# EP4CE6E22C8.net
KiCad netlist of a schematic drawn in Altium Designer
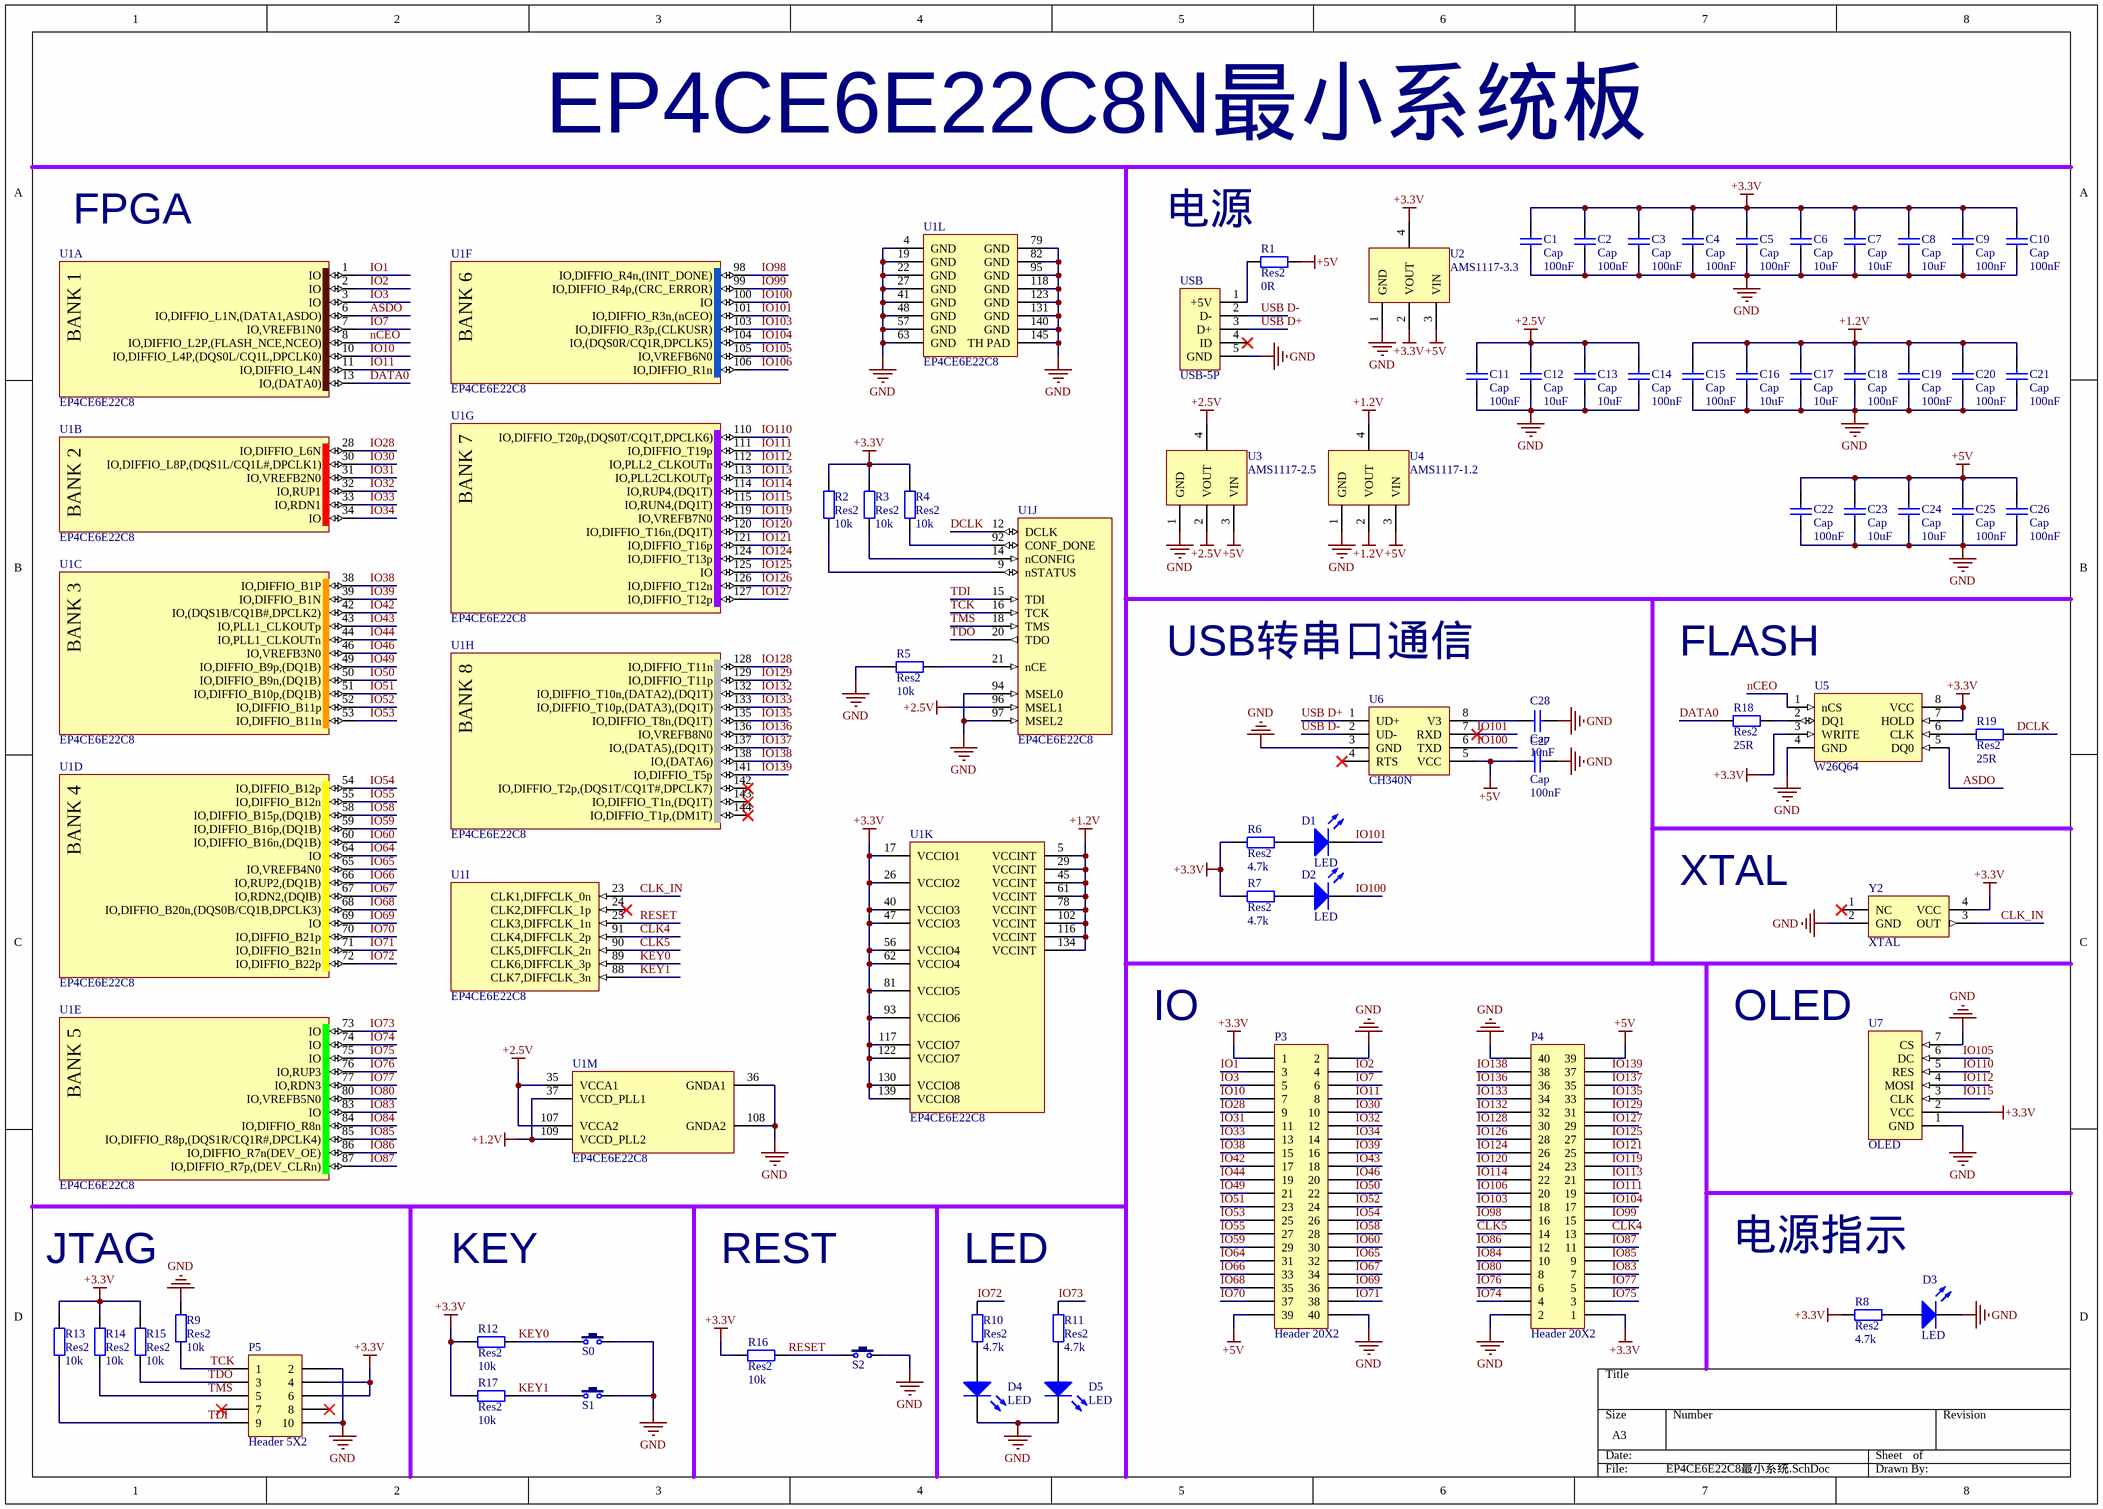
[diagram p0: EP4CE6E22C8最小系统.SchDoc]

(export (version "E")
  (design (tool "Eeschema 10.0.6"))
  (components
    (comp (ref "C1")
      (value "Cap")
      (footprint "C 0603")
      (description "Capacitor")
      (fields (field (name "ALTIUM_VALUE") "100nF") (field (name "PUBLISHER") "Altium Limited"))
      (libsource (lib "Miscellaneous Devices") (part "Cap"))
    )
    (comp (ref "C2")
      (value "Cap")
      (footprint "C 0603")
      (description "Capacitor")
      (fields (field (name "ALTIUM_VALUE") "100nF") (field (name "PUBLISHER") "Altium Limited"))
      (libsource (lib "Miscellaneous Devices") (part "Cap"))
    )
    (comp (ref "C3")
      (value "Cap")
      (footprint "C 0603")
      (description "Capacitor")
      (fields (field (name "ALTIUM_VALUE") "100nF") (field (name "PUBLISHER") "Altium Limited"))
      (libsource (lib "Miscellaneous Devices") (part "Cap"))
    )
    (comp (ref "C4")
      (value "Cap")
      (footprint "C 0603")
      (description "Capacitor")
      (fields (field (name "ALTIUM_VALUE") "100nF") (field (name "PUBLISHER") "Altium Limited"))
      (libsource (lib "Miscellaneous Devices") (part "Cap"))
    )
    (comp (ref "C5")
      (value "Cap")
      (footprint "C 0603")
      (description "Capacitor")
      (fields (field (name "ALTIUM_VALUE") "100nF") (field (name "PUBLISHER") "Altium Limited"))
      (libsource (lib "Miscellaneous Devices") (part "Cap"))
    )
    (comp (ref "C6")
      (value "Cap")
      (footprint "C 0603")
      (description "Capacitor")
      (fields (field (name "ALTIUM_VALUE") "10uF") (field (name "PUBLISHER") "Altium Limited"))
      (libsource (lib "Miscellaneous Devices") (part "Cap"))
    )
    (comp (ref "C7")
      (value "Cap")
      (footprint "C 0603")
      (description "Capacitor")
      (fields (field (name "ALTIUM_VALUE") "10uF") (field (name "PUBLISHER") "Altium Limited"))
      (libsource (lib "Miscellaneous Devices") (part "Cap"))
    )
    (comp (ref "C8")
      (value "Cap")
      (footprint "C 0603")
      (description "Capacitor")
      (fields (field (name "ALTIUM_VALUE") "10uF") (field (name "PUBLISHER") "Altium Limited"))
      (libsource (lib "Miscellaneous Devices") (part "Cap"))
    )
    (comp (ref "C9")
      (value "Cap")
      (footprint "C 0603")
      (description "Capacitor")
      (fields (field (name "ALTIUM_VALUE") "100nF") (field (name "PUBLISHER") "Altium Limited"))
      (libsource (lib "Miscellaneous Devices") (part "Cap"))
    )
    (comp (ref "C10")
      (value "Cap")
      (footprint "C 0603")
      (description "Capacitor")
      (fields (field (name "ALTIUM_VALUE") "100nF") (field (name "PUBLISHER") "Altium Limited"))
      (libsource (lib "Miscellaneous Devices") (part "Cap"))
    )
    (comp (ref "C11")
      (value "Cap")
      (footprint "C 0603")
      (description "Capacitor")
      (fields (field (name "ALTIUM_VALUE") "100nF") (field (name "PUBLISHER") "Altium Limited"))
      (libsource (lib "Miscellaneous Devices") (part "Cap"))
    )
    (comp (ref "C12")
      (value "Cap")
      (footprint "C 0603")
      (description "Capacitor")
      (fields (field (name "ALTIUM_VALUE") "10uF") (field (name "PUBLISHER") "Altium Limited"))
      (libsource (lib "Miscellaneous Devices") (part "Cap"))
    )
    (comp (ref "C13")
      (value "Cap")
      (footprint "C 0603")
      (description "Capacitor")
      (fields (field (name "ALTIUM_VALUE") "10uF") (field (name "PUBLISHER") "Altium Limited"))
      (libsource (lib "Miscellaneous Devices") (part "Cap"))
    )
    (comp (ref "C14")
      (value "Cap")
      (footprint "C 0603")
      (description "Capacitor")
      (fields (field (name "ALTIUM_VALUE") "100nF") (field (name "PUBLISHER") "Altium Limited"))
      (libsource (lib "Miscellaneous Devices") (part "Cap"))
    )
    (comp (ref "C15")
      (value "Cap")
      (footprint "C 0603")
      (description "Capacitor")
      (fields (field (name "ALTIUM_VALUE") "100nF") (field (name "PUBLISHER") "Altium Limited"))
      (libsource (lib "Miscellaneous Devices") (part "Cap"))
    )
    (comp (ref "C16")
      (value "Cap")
      (footprint "C 0603")
      (description "Capacitor")
      (fields (field (name "ALTIUM_VALUE") "10uF") (field (name "PUBLISHER") "Altium Limited"))
      (libsource (lib "Miscellaneous Devices") (part "Cap"))
    )
    (comp (ref "C17")
      (value "Cap")
      (footprint "C 0603")
      (description "Capacitor")
      (fields (field (name "ALTIUM_VALUE") "10uF") (field (name "PUBLISHER") "Altium Limited"))
      (libsource (lib "Miscellaneous Devices") (part "Cap"))
    )
    (comp (ref "C18")
      (value "Cap")
      (footprint "C 0603")
      (description "Capacitor")
      (fields (field (name "ALTIUM_VALUE") "100nF") (field (name "PUBLISHER") "Altium Limited"))
      (libsource (lib "Miscellaneous Devices") (part "Cap"))
    )
    (comp (ref "C19")
      (value "Cap")
      (footprint "C 0603")
      (description "Capacitor")
      (fields (field (name "ALTIUM_VALUE") "100nF") (field (name "PUBLISHER") "Altium Limited"))
      (libsource (lib "Miscellaneous Devices") (part "Cap"))
    )
    (comp (ref "C20")
      (value "Cap")
      (footprint "C 0603")
      (description "Capacitor")
      (fields (field (name "ALTIUM_VALUE") "100nF") (field (name "PUBLISHER") "Altium Limited"))
      (libsource (lib "Miscellaneous Devices") (part "Cap"))
    )
    (comp (ref "C21")
      (value "Cap")
      (footprint "C 0603")
      (description "Capacitor")
      (fields (field (name "ALTIUM_VALUE") "100nF") (field (name "PUBLISHER") "Altium Limited"))
      (libsource (lib "Miscellaneous Devices") (part "Cap"))
    )
    (comp (ref "C22")
      (value "Cap")
      (footprint "C 0603")
      (description "Capacitor")
      (fields (field (name "ALTIUM_VALUE") "100nF") (field (name "PUBLISHER") "Altium Limited"))
      (libsource (lib "Miscellaneous Devices") (part "Cap"))
    )
    (comp (ref "C23")
      (value "Cap")
      (footprint "C 0603")
      (description "Capacitor")
      (fields (field (name "ALTIUM_VALUE") "10uF") (field (name "PUBLISHER") "Altium Limited"))
      (libsource (lib "Miscellaneous Devices") (part "Cap"))
    )
    (comp (ref "C24")
      (value "Cap")
      (footprint "C 0603")
      (description "Capacitor")
      (fields (field (name "ALTIUM_VALUE") "10uF") (field (name "PUBLISHER") "Altium Limited"))
      (libsource (lib "Miscellaneous Devices") (part "Cap"))
    )
    (comp (ref "C25")
      (value "Cap")
      (footprint "C 0603")
      (description "Capacitor")
      (fields (field (name "ALTIUM_VALUE") "100nF") (field (name "PUBLISHER") "Altium Limited"))
      (libsource (lib "Miscellaneous Devices") (part "Cap"))
    )
    (comp (ref "C26")
      (value "Cap")
      (footprint "C 0603")
      (description "Capacitor")
      (fields (field (name "ALTIUM_VALUE") "100nF") (field (name "PUBLISHER") "Altium Limited"))
      (libsource (lib "Miscellaneous Devices") (part "Cap"))
    )
    (comp (ref "C27")
      (value "Cap")
      (footprint "C 0603")
      (description "Capacitor (Semiconductor SIM Model)")
      (fields (field (name "ALTIUM_VALUE") "100nF") (field (name "PUBLISHER") "Altium Limited"))
      (libsource (lib "我的元件库") (part "Cap Semi"))
    )
    (comp (ref "C28")
      (value "Cap")
      (footprint "C 0603")
      (description "Capacitor (Semiconductor SIM Model)")
      (fields (field (name "ALTIUM_VALUE") "10nF") (field (name "PUBLISHER") "Altium Limited"))
      (libsource (lib "我的元件库") (part "Cap Semi"))
    )
    (comp (ref "D1")
      (value "LED")
      (footprint "LED 0805R")
      (description "Typical INFRARED GaAs LED")
      (fields (field (name "PUBLISHER") "Altium Limited"))
      (libsource (lib "Miscellaneous Devices") (part "LED0"))
    )
    (comp (ref "D2")
      (value "LED")
      (footprint "LED 0805R")
      (description "Typical INFRARED GaAs LED")
      (fields (field (name "PUBLISHER") "Altium Limited"))
      (libsource (lib "Miscellaneous Devices") (part "LED0"))
    )
    (comp (ref "D3")
      (value "LED")
      (footprint "LED 0805R")
      (description "Typical INFRARED GaAs LED")
      (fields (field (name "PUBLISHER") "Altium Limited"))
      (libsource (lib "Miscellaneous Devices") (part "LED0"))
    )
    (comp (ref "D4")
      (value "LED")
      (footprint "LED 0805R")
      (description "Typical INFRARED GaAs LED")
      (fields (field (name "PUBLISHER") "Altium Limited"))
      (libsource (lib "Miscellaneous Devices") (part "LED0"))
    )
    (comp (ref "D5")
      (value "LED")
      (footprint "LED 0805R")
      (description "Typical INFRARED GaAs LED")
      (fields (field (name "PUBLISHER") "Altium Limited"))
      (libsource (lib "Miscellaneous Devices") (part "LED0"))
    )
    (comp (ref "P3")
      (value "Header 20X2")
      (footprint "HDR-20X2")
      (description "Header, 20-Pin, Dual row")
      (fields (field (name "PUBLISHER") "Altium Limited"))
      (libsource (lib "Miscellaneous Connectors") (part "Header 20X2"))
    )
    (comp (ref "P4")
      (value "Header 20X2")
      (footprint "HDR-20X2")
      (description "Header, 20-Pin, Dual row")
      (fields (field (name "PUBLISHER") "Altium Limited"))
      (libsource (lib "") (part "Header 20X2_1"))
    )
    (comp (ref "P5")
      (value "Header 5X2")
      (footprint "牛角座10p")
      (description "Header, 5-Pin, Dual row")
      (fields (field (name "PUBLISHER") "Altium Limited"))
      (libsource (lib "Miscellaneous Connectors") (part "Header 5X2"))
    )
    (comp (ref "R1")
      (value "Res2")
      (footprint "R 0805-HP")
      (description "Resistor")
      (fields (field (name "ALTIUM_VALUE") "0R") (field (name "PUBLISHER") "Altium Limited"))
      (libsource (lib "") (part "Res2_2"))
    )
    (comp (ref "R2")
      (value "Res2")
      (footprint "R 0805-HP")
      (description "Resistor")
      (fields (field (name "ALTIUM_VALUE") "10k") (field (name "PUBLISHER") "Altium Limited"))
      (libsource (lib "Miscellaneous Devices") (part "Res2"))
    )
    (comp (ref "R3")
      (value "Res2")
      (footprint "R 0805-HP")
      (description "Resistor")
      (fields (field (name "ALTIUM_VALUE") "10k") (field (name "PUBLISHER") "Altium Limited"))
      (libsource (lib "Miscellaneous Devices") (part "Res2"))
    )
    (comp (ref "R4")
      (value "Res2")
      (footprint "R 0805-HP")
      (description "Resistor")
      (fields (field (name "ALTIUM_VALUE") "10k") (field (name "PUBLISHER") "Altium Limited"))
      (libsource (lib "Miscellaneous Devices") (part "Res2"))
    )
    (comp (ref "R5")
      (value "Res2")
      (footprint "R 0805-HP")
      (description "Resistor")
      (fields (field (name "ALTIUM_VALUE") "10k") (field (name "PUBLISHER") "Altium Limited"))
      (libsource (lib "") (part "Res2_2"))
    )
    (comp (ref "R6")
      (value "Res2")
      (footprint "R 0805-HP")
      (description "Resistor")
      (fields (field (name "ALTIUM_VALUE") "4.7k") (field (name "PUBLISHER") "Altium Limited"))
      (libsource (lib "") (part "Res2_1"))
    )
    (comp (ref "R7")
      (value "Res2")
      (footprint "R 0805-HP")
      (description "Resistor")
      (fields (field (name "ALTIUM_VALUE") "4.7k") (field (name "PUBLISHER") "Altium Limited"))
      (libsource (lib "") (part "Res2_1"))
    )
    (comp (ref "R8")
      (value "Res2")
      (footprint "R 0805-HP")
      (description "Resistor")
      (fields (field (name "ALTIUM_VALUE") "4.7k") (field (name "PUBLISHER") "Altium Limited"))
      (libsource (lib "") (part "Res2_1"))
    )
    (comp (ref "R9")
      (value "Res2")
      (footprint "R 0805-HP")
      (description "Resistor")
      (fields (field (name "ALTIUM_VALUE") "10k") (field (name "PUBLISHER") "Altium Limited"))
      (libsource (lib "Miscellaneous Devices") (part "Res2"))
    )
    (comp (ref "R10")
      (value "Res2")
      (footprint "R 0805-HP")
      (description "Resistor")
      (fields (field (name "ALTIUM_VALUE") "4.7k") (field (name "PUBLISHER") "Altium Limited"))
      (libsource (lib "") (part "Res2_3"))
    )
    (comp (ref "R11")
      (value "Res2")
      (footprint "R 0805-HP")
      (description "Resistor")
      (fields (field (name "ALTIUM_VALUE") "4.7k") (field (name "PUBLISHER") "Altium Limited"))
      (libsource (lib "") (part "Res2_3"))
    )
    (comp (ref "R12")
      (value "Res2")
      (footprint "R 0805-HP")
      (description "Resistor")
      (fields (field (name "ALTIUM_VALUE") "10k") (field (name "PUBLISHER") "Altium Limited"))
      (libsource (lib "") (part "Res2_2"))
    )
    (comp (ref "R13")
      (value "Res2")
      (footprint "R 0805-HP")
      (description "Resistor")
      (fields (field (name "ALTIUM_VALUE") "10k") (field (name "PUBLISHER") "Altium Limited"))
      (libsource (lib "Miscellaneous Devices") (part "Res2"))
    )
    (comp (ref "R14")
      (value "Res2")
      (footprint "R 0805-HP")
      (description "Resistor")
      (fields (field (name "ALTIUM_VALUE") "10k") (field (name "PUBLISHER") "Altium Limited"))
      (libsource (lib "Miscellaneous Devices") (part "Res2"))
    )
    (comp (ref "R15")
      (value "Res2")
      (footprint "R 0805-HP")
      (description "Resistor")
      (fields (field (name "ALTIUM_VALUE") "10k") (field (name "PUBLISHER") "Altium Limited"))
      (libsource (lib "Miscellaneous Devices") (part "Res2"))
    )
    (comp (ref "R16")
      (value "Res2")
      (footprint "R 0805-HP")
      (description "Resistor")
      (fields (field (name "ALTIUM_VALUE") "10k") (field (name "PUBLISHER") "Altium Limited"))
      (libsource (lib "") (part "Res2_2"))
    )
    (comp (ref "R17")
      (value "Res2")
      (footprint "R 0805-HP")
      (description "Resistor")
      (fields (field (name "ALTIUM_VALUE") "10k") (field (name "PUBLISHER") "Altium Limited"))
      (libsource (lib "") (part "Res2_2"))
    )
    (comp (ref "R18")
      (value "Res2")
      (footprint "R 0805-HP")
      (description "Resistor")
      (fields (field (name "ALTIUM_VALUE") "25R") (field (name "PUBLISHER") "Altium Limited"))
      (libsource (lib "") (part "Res2_1"))
    )
    (comp (ref "R19")
      (value "Res2")
      (footprint "R 0805-HP")
      (description "Resistor")
      (fields (field (name "ALTIUM_VALUE") "25R") (field (name "PUBLISHER") "Altium Limited"))
      (libsource (lib "") (part "Res2_1"))
    )
    (comp (ref "S0")
      (value "3x6x5")
      (footprint "TSW SMD-3*6*2.5")
      (description "3x6轻触开关")
      (fields (field (name "版权归属") "黎明电子style"))
      (libsource (lib "按键-开关") (part "TSW 3x6"))
    )
    (comp (ref "S1")
      (value "3x6x5")
      (footprint "TSW SMD-3*6*2.5")
      (description "3x6轻触开关")
      (fields (field (name "版权归属") "黎明电子style"))
      (libsource (lib "按键-开关") (part "TSW 3x6"))
    )
    (comp (ref "S2")
      (value "3x6x5")
      (footprint "TSW SMD-3*6*2.5")
      (description "3x6轻触开关")
      (fields (field (name "版权归属") "黎明电子style"))
      (libsource (lib "按键-开关") (part "TSW 3x6"))
    )
    (comp (ref "U1")
      (value "EP4CE6E22C8")
      (footprint "EQFP144_M")
      (description "CYCLONE IV E  FPGA EP4CE6E22C8 144Pins speed 8")
      (libsource (lib "我的元件库") (part "EP4CE6E22C8"))
    )
    (comp (ref "U2")
      (value "AMS1117-3.3")
      (footprint "SOT:SOT223_M")
      (description "3.3Voutput,4.3-12Vinput LDO")
      (libsource (lib "我的元件库") (part "AMS1117"))
    )
    (comp (ref "U3")
      (value "AMS1117-2.5")
      (footprint "SOT:SOT223_M")
      (description "3.3Voutput,4.3-12Vinput LDO")
      (libsource (lib "我的元件库") (part "AMS1117"))
    )
    (comp (ref "U4")
      (value "AMS1117-1.2")
      (footprint "SOT:SOT223_M")
      (description "3.3Voutput,4.3-12Vinput LDO")
      (libsource (lib "我的元件库") (part "AMS1117"))
    )
    (comp (ref "U5")
      (value "W26Q64")
      (footprint "SOP8_M")
      (description "FLASH")
      (libsource (lib "我的元件库") (part "W25Q64"))
    )
    (comp (ref "U6")
      (value "CH340N")
      (footprint "SOP8_M")
      (libsource (lib "EP4CE6E22C8最小系统") (part "CH340G"))
    )
    (comp (ref "U7")
      (value "OLED")
      (footprint "HDR-1X7_M")
      (description "1.3寸或0.96寸SPI接口的OLED")
      (libsource (lib "我的元件库") (part "OLED_SPI"))
    )
    (comp (ref "USB")
      (value "USB-5P")
      (footprint "USB-MICRO_B")
      (description "微型USB母座")
      (fields (field (name "版权归属") "黎明电子style"))
      (libsource (lib "接口类") (part "USB-5P"))
    )
    (comp (ref "Y2") (value "XTAL") (footprint "XTAL-3225") (libsource (lib "我的元件库") (part "有源晶振")))
  )
  (nets
    (net (code "1") (name "+1.2V") (class "Default")
      (node (ref "C15") (pin "2") (pinfunction "2_2") (pintype "passive"))
      (node (ref "C16") (pin "2") (pinfunction "2_2") (pintype "passive"))
      (node (ref "C17") (pin "2") (pinfunction "2_2") (pintype "passive"))
      (node (ref "C18") (pin "2") (pinfunction "2_2") (pintype "passive"))
      (node (ref "C19") (pin "2") (pinfunction "2_2") (pintype "passive"))
      (node (ref "C20") (pin "2") (pinfunction "2_2") (pintype "passive"))
      (node (ref "C21") (pin "2") (pinfunction "2_2") (pintype "passive"))
      (node (ref "U1") (pin "102") (pinfunction "VCCINT_102") (pintype "power_in"))
      (node (ref "U1") (pin "109") (pinfunction "VCCD_PLL2_109") (pintype "power_in"))
      (node (ref "U1") (pin "116") (pinfunction "VCCINT_116") (pintype "power_in"))
      (node (ref "U1") (pin "134") (pinfunction "VCCINT_134") (pintype "power_in"))
      (node (ref "U1") (pin "29") (pinfunction "VCCINT_29") (pintype "power_in"))
      (node (ref "U1") (pin "37") (pinfunction "VCCD_PLL1_37") (pintype "power_in"))
      (node (ref "U1") (pin "45") (pinfunction "VCCINT_45") (pintype "power_in"))
      (node (ref "U1") (pin "5") (pinfunction "VCCINT_5") (pintype "power_in"))
      (node (ref "U1") (pin "61") (pinfunction "VCCINT_61") (pintype "power_in"))
      (node (ref "U1") (pin "78") (pinfunction "VCCINT_78") (pintype "power_in"))
      (node (ref "U4") (pin "2") (pinfunction "VOUT_2") (pintype "passive"))
      (node (ref "U4") (pin "4") (pinfunction "VOUT_4") (pintype "passive"))
    )
    (net (code "2") (name "+2.5V") (class "Default")
      (node (ref "C11") (pin "2") (pinfunction "2_2") (pintype "passive"))
      (node (ref "C12") (pin "2") (pinfunction "2_2") (pintype "passive"))
      (node (ref "C13") (pin "2") (pinfunction "2_2") (pintype "passive"))
      (node (ref "C14") (pin "2") (pinfunction "2_2") (pintype "passive"))
      (node (ref "U1") (pin "107") (pinfunction "VCCA2_107") (pintype "power_in"))
      (node (ref "U1") (pin "35") (pinfunction "VCCA1_35") (pintype "power_in"))
      (node (ref "U1") (pin "96") (pinfunction "MSEL1_96") (pintype "input"))
      (node (ref "U3") (pin "2") (pinfunction "VOUT_2") (pintype "passive"))
      (node (ref "U3") (pin "4") (pinfunction "VOUT_4") (pintype "passive"))
    )
    (net (code "3") (name "+3.3V") (class "Default")
      (node (ref "C1") (pin "2") (pinfunction "2_2") (pintype "passive"))
      (node (ref "C10") (pin "2") (pinfunction "2_2") (pintype "passive"))
      (node (ref "C2") (pin "2") (pinfunction "2_2") (pintype "passive"))
      (node (ref "C3") (pin "2") (pinfunction "2_2") (pintype "passive"))
      (node (ref "C4") (pin "2") (pinfunction "2_2") (pintype "passive"))
      (node (ref "C5") (pin "2") (pinfunction "2_2") (pintype "passive"))
      (node (ref "C6") (pin "2") (pinfunction "2_2") (pintype "passive"))
      (node (ref "C7") (pin "2") (pinfunction "2_2") (pintype "passive"))
      (node (ref "C8") (pin "2") (pinfunction "2_2") (pintype "passive"))
      (node (ref "C9") (pin "2") (pinfunction "2_2") (pintype "passive"))
      (node (ref "P3") (pin "1") (pinfunction "1_1") (pintype "passive"))
      (node (ref "P4") (pin "1") (pinfunction "1_1") (pintype "passive"))
      (node (ref "P5") (pin "4") (pinfunction "4_4") (pintype "passive"))
      (node (ref "P5") (pin "6") (pinfunction "6_6") (pintype "passive"))
      (node (ref "R12") (pin "1") (pinfunction "1_1") (pintype "passive"))
      (node (ref "R13") (pin "1") (pinfunction "1_1") (pintype "passive"))
      (node (ref "R14") (pin "1") (pinfunction "1_1") (pintype "passive"))
      (node (ref "R15") (pin "1") (pinfunction "1_1") (pintype "passive"))
      (node (ref "R16") (pin "1") (pinfunction "1_1") (pintype "passive"))
      (node (ref "R17") (pin "1") (pinfunction "1_1") (pintype "passive"))
      (node (ref "R2") (pin "1") (pinfunction "1_1") (pintype "passive"))
      (node (ref "R3") (pin "1") (pinfunction "1_1") (pintype "passive"))
      (node (ref "R4") (pin "1") (pinfunction "1_1") (pintype "passive"))
      (node (ref "R6") (pin "2") (pinfunction "2_2") (pintype "passive"))
      (node (ref "R7") (pin "2") (pinfunction "2_2") (pintype "passive"))
      (node (ref "R8") (pin "2") (pinfunction "2_2") (pintype "passive"))
      (node (ref "U1") (pin "117") (pinfunction "VCCIO7_117") (pintype "power_in"))
      (node (ref "U1") (pin "122") (pinfunction "VCCIO7_122") (pintype "power_in"))
      (node (ref "U1") (pin "130") (pinfunction "VCCIO8_130") (pintype "power_in"))
      (node (ref "U1") (pin "139") (pinfunction "VCCIO8_139") (pintype "power_in"))
      (node (ref "U1") (pin "17") (pinfunction "VCCIO1_17") (pintype "power_in"))
      (node (ref "U1") (pin "26") (pinfunction "VCCIO2_26") (pintype "power_in"))
      (node (ref "U1") (pin "40") (pinfunction "VCCIO3_40") (pintype "power_in"))
      (node (ref "U1") (pin "47") (pinfunction "VCCIO3_47") (pintype "power_in"))
      (node (ref "U1") (pin "56") (pinfunction "VCCIO4_56") (pintype "power_in"))
      (node (ref "U1") (pin "62") (pinfunction "VCCIO4_62") (pintype "power_in"))
      (node (ref "U1") (pin "81") (pinfunction "VCCIO5_81") (pintype "power_in"))
      (node (ref "U1") (pin "93") (pinfunction "VCCIO6_93") (pintype "power_in"))
      (node (ref "U2") (pin "2") (pinfunction "VOUT_2") (pintype "passive"))
      (node (ref "U2") (pin "4") (pinfunction "VOUT_4") (pintype "passive"))
      (node (ref "U5") (pin "3") (pinfunction "WRITE_3") (pintype "input"))
      (node (ref "U5") (pin "7") (pinfunction "HOLD_7") (pintype "input"))
      (node (ref "U5") (pin "8") (pinfunction "VCC_8") (pintype "passive"))
      (node (ref "U7") (pin "2") (pinfunction "VCC_2") (pintype "power_in"))
      (node (ref "Y2") (pin "4") (pinfunction "VCC_4") (pintype "power_in"))
    )
    (net (code "4") (name "+5V") (class "Default")
      (node (ref "C22") (pin "2") (pinfunction "2_2") (pintype "passive"))
      (node (ref "C23") (pin "2") (pinfunction "2_2") (pintype "passive"))
      (node (ref "C24") (pin "2") (pinfunction "2_2") (pintype "passive"))
      (node (ref "C25") (pin "2") (pinfunction "2_2") (pintype "passive"))
      (node (ref "C26") (pin "2") (pinfunction "2_2") (pintype "passive"))
      (node (ref "C27") (pin "2") (pinfunction "2_2") (pintype "passive"))
      (node (ref "P3") (pin "39") (pinfunction "39_39") (pintype "passive"))
      (node (ref "P4") (pin "39") (pinfunction "39_39") (pintype "passive"))
      (node (ref "R1") (pin "2") (pinfunction "2_2") (pintype "passive"))
      (node (ref "U2") (pin "3") (pinfunction "VIN_3") (pintype "passive"))
      (node (ref "U3") (pin "3") (pinfunction "VIN_3") (pintype "passive"))
      (node (ref "U4") (pin "3") (pinfunction "VIN_3") (pintype "passive"))
      (node (ref "U6") (pin "5") (pinfunction "VCC_5") (pintype "passive"))
    )
    (net (code "5") (name "/ASDO") (class "Default")
      (node (ref "U1") (pin "6") (pinfunction "IO,DIFFIO_L1N,(DATA1,ASDO)_6") (pintype "bidirectional"))
      (node (ref "U5") (pin "5") (pinfunction "DQ0_5") (pintype "input"))
    )
    (net (code "6") (name "/CLK4") (class "Default")
      (node (ref "P4") (pin "13") (pinfunction "13_13") (pintype "passive"))
      (node (ref "U1") (pin "91") (pinfunction "CLK4,DIFFCLK_2p_91") (pintype "input"))
    )
    (net (code "7") (name "/CLK5") (class "Default")
      (node (ref "P4") (pin "14") (pinfunction "14_14") (pintype "passive"))
      (node (ref "U1") (pin "90") (pinfunction "CLK5,DIFFCLK_2n_90") (pintype "input"))
    )
    (net (code "8") (name "/CLK_IN") (class "Default")
      (node (ref "U1") (pin "23") (pinfunction "CLK1,DIFFCLK_0n_23") (pintype "input"))
      (node (ref "Y2") (pin "3") (pinfunction "OUT_3") (pintype "output"))
    )
    (net (code "9") (name "/DATA0") (class "Default")
      (node (ref "R18") (pin "2") (pinfunction "2_2") (pintype "passive"))
      (node (ref "U1") (pin "13") (pinfunction "IO,(DATA0)_13") (pintype "bidirectional"))
    )
    (net (code "10") (name "/DCLK") (class "Default")
      (node (ref "R19") (pin "1") (pinfunction "1_1") (pintype "passive"))
      (node (ref "U1") (pin "12") (pinfunction "DCLK_12") (pintype "bidirectional"))
    )
    (net (code "11") (name "/IO1") (class "Default")
      (node (ref "P3") (pin "3") (pinfunction "3_3") (pintype "passive"))
      (node (ref "U1") (pin "1") (pinfunction "IO_1") (pintype "bidirectional"))
    )
    (net (code "12") (name "/IO2") (class "Default")
      (node (ref "P3") (pin "4") (pinfunction "4_4") (pintype "passive"))
      (node (ref "U1") (pin "2") (pinfunction "IO_2") (pintype "bidirectional"))
    )
    (net (code "13") (name "/IO3") (class "Default")
      (node (ref "P3") (pin "5") (pinfunction "5_5") (pintype "passive"))
      (node (ref "U1") (pin "3") (pinfunction "IO_3") (pintype "bidirectional"))
    )
    (net (code "14") (name "/IO7") (class "Default")
      (node (ref "P3") (pin "6") (pinfunction "6_6") (pintype "passive"))
      (node (ref "U1") (pin "7") (pinfunction "IO,VREFB1N0_7") (pintype "bidirectional"))
    )
    (net (code "15") (name "/IO10") (class "Default")
      (node (ref "P3") (pin "7") (pinfunction "7_7") (pintype "passive"))
      (node (ref "U1") (pin "10") (pinfunction "IO,DIFFIO_L4P,(DQS0L/CQ1L,DPCLK0)_10") (pintype "bidirectional"))
    )
    (net (code "16") (name "/IO11") (class "Default")
      (node (ref "P3") (pin "8") (pinfunction "8_8") (pintype "passive"))
      (node (ref "U1") (pin "11") (pinfunction "IO,DIFFIO_L4N_11") (pintype "bidirectional"))
    )
    (net (code "17") (name "/IO28") (class "Default")
      (node (ref "P3") (pin "9") (pinfunction "9_9") (pintype "passive"))
      (node (ref "U1") (pin "28") (pinfunction "IO,DIFFIO_L6N_28") (pintype "bidirectional"))
    )
    (net (code "18") (name "/IO30") (class "Default")
      (node (ref "P3") (pin "10") (pinfunction "10_10") (pintype "passive"))
      (node (ref "U1") (pin "30") (pinfunction "IO,DIFFIO_L8P,(DQS1L/CQ1L#,DPCLK1)_30") (pintype "bidirectional"))
    )
    (net (code "19") (name "/IO31") (class "Default")
      (node (ref "P3") (pin "11") (pinfunction "11_11") (pintype "passive"))
      (node (ref "U1") (pin "31") (pinfunction "IO,VREFB2N0_31") (pintype "bidirectional"))
    )
    (net (code "20") (name "/IO32") (class "Default")
      (node (ref "P3") (pin "12") (pinfunction "12_12") (pintype "passive"))
      (node (ref "U1") (pin "32") (pinfunction "IO,RUP1_32") (pintype "bidirectional"))
    )
    (net (code "21") (name "/IO33") (class "Default")
      (node (ref "P3") (pin "13") (pinfunction "13_13") (pintype "passive"))
      (node (ref "U1") (pin "33") (pinfunction "IO,RDN1_33") (pintype "bidirectional"))
    )
    (net (code "22") (name "/IO34") (class "Default")
      (node (ref "P3") (pin "14") (pinfunction "14_14") (pintype "passive"))
      (node (ref "U1") (pin "34") (pinfunction "IO_34") (pintype "bidirectional"))
    )
    (net (code "23") (name "/IO38") (class "Default")
      (node (ref "P3") (pin "15") (pinfunction "15_15") (pintype "passive"))
      (node (ref "U1") (pin "38") (pinfunction "IO,DIFFIO_B1P_38") (pintype "bidirectional"))
    )
    (net (code "24") (name "/IO39") (class "Default")
      (node (ref "P3") (pin "16") (pinfunction "16_16") (pintype "passive"))
      (node (ref "U1") (pin "39") (pinfunction "IO,DIFFIO_B1N_39") (pintype "bidirectional"))
    )
    (net (code "25") (name "/IO42") (class "Default")
      (node (ref "P3") (pin "17") (pinfunction "17_17") (pintype "passive"))
      (node (ref "U1") (pin "42") (pinfunction "IO,(DQS1B/CQ1B#,DPCLK2)_42") (pintype "bidirectional"))
    )
    (net (code "26") (name "/IO43") (class "Default")
      (node (ref "P3") (pin "18") (pinfunction "18_18") (pintype "passive"))
      (node (ref "U1") (pin "43") (pinfunction "IO,PLL1_CLKOUTp_43") (pintype "bidirectional"))
    )
    (net (code "27") (name "/IO44") (class "Default")
      (node (ref "P3") (pin "19") (pinfunction "19_19") (pintype "passive"))
      (node (ref "U1") (pin "44") (pinfunction "IO,PLL1_CLKOUTn_44") (pintype "bidirectional"))
    )
    (net (code "28") (name "/IO46") (class "Default")
      (node (ref "P3") (pin "20") (pinfunction "20_20") (pintype "passive"))
      (node (ref "U1") (pin "46") (pinfunction "IO,VREFB3N0_46") (pintype "bidirectional"))
    )
    (net (code "29") (name "/IO49") (class "Default")
      (node (ref "P3") (pin "21") (pinfunction "21_21") (pintype "passive"))
      (node (ref "U1") (pin "49") (pinfunction "IO,DIFFIO_B9p,(DQ1B)_49") (pintype "bidirectional"))
    )
    (net (code "30") (name "/IO50") (class "Default")
      (node (ref "P3") (pin "22") (pinfunction "22_22") (pintype "passive"))
      (node (ref "U1") (pin "50") (pinfunction "IO,DIFFIO_B9n,(DQ1B)_50") (pintype "bidirectional"))
    )
    (net (code "31") (name "/IO51") (class "Default")
      (node (ref "P3") (pin "23") (pinfunction "23_23") (pintype "passive"))
      (node (ref "U1") (pin "51") (pinfunction "IO,DIFFIO_B10p,(DQ1B)_51") (pintype "bidirectional"))
    )
    (net (code "32") (name "/IO52") (class "Default")
      (node (ref "P3") (pin "24") (pinfunction "24_24") (pintype "passive"))
      (node (ref "U1") (pin "52") (pinfunction "IO,DIFFIO_B11p_52") (pintype "bidirectional"))
    )
    (net (code "33") (name "/IO53") (class "Default")
      (node (ref "P3") (pin "25") (pinfunction "25_25") (pintype "passive"))
      (node (ref "U1") (pin "53") (pinfunction "IO,DIFFIO_B11n_53") (pintype "bidirectional"))
    )
    (net (code "34") (name "/IO54") (class "Default")
      (node (ref "P3") (pin "26") (pinfunction "26_26") (pintype "passive"))
      (node (ref "U1") (pin "54") (pinfunction "IO,DIFFIO_B12p_54") (pintype "bidirectional"))
    )
    (net (code "35") (name "/IO55") (class "Default")
      (node (ref "P3") (pin "27") (pinfunction "27_27") (pintype "passive"))
      (node (ref "U1") (pin "55") (pinfunction "IO,DIFFIO_B12n_55") (pintype "bidirectional"))
    )
    (net (code "36") (name "/IO58") (class "Default")
      (node (ref "P3") (pin "28") (pinfunction "28_28") (pintype "passive"))
      (node (ref "U1") (pin "58") (pinfunction "IO,DIFFIO_B15p,(DQ1B)_58") (pintype "bidirectional"))
    )
    (net (code "37") (name "/IO59") (class "Default")
      (node (ref "P3") (pin "29") (pinfunction "29_29") (pintype "passive"))
      (node (ref "U1") (pin "59") (pinfunction "IO,DIFFIO_B16p,(DQ1B)_59") (pintype "bidirectional"))
    )
    (net (code "38") (name "/IO60") (class "Default")
      (node (ref "P3") (pin "30") (pinfunction "30_30") (pintype "passive"))
      (node (ref "U1") (pin "60") (pinfunction "IO,DIFFIO_B16n,(DQ1B)_60") (pintype "bidirectional"))
    )
    (net (code "39") (name "/IO64") (class "Default")
      (node (ref "P3") (pin "31") (pinfunction "31_31") (pintype "passive"))
      (node (ref "U1") (pin "64") (pinfunction "IO_64") (pintype "bidirectional"))
    )
    (net (code "40") (name "/IO65") (class "Default")
      (node (ref "P3") (pin "32") (pinfunction "32_32") (pintype "passive"))
      (node (ref "U1") (pin "65") (pinfunction "IO,VREFB4N0_65") (pintype "bidirectional"))
    )
    (net (code "41") (name "/IO66") (class "Default")
      (node (ref "P3") (pin "33") (pinfunction "33_33") (pintype "passive"))
      (node (ref "U1") (pin "66") (pinfunction "IO,RUP2,(DQ1B)_66") (pintype "bidirectional"))
    )
    (net (code "42") (name "/IO67") (class "Default")
      (node (ref "P3") (pin "34") (pinfunction "34_34") (pintype "passive"))
      (node (ref "U1") (pin "67") (pinfunction "IO,RDN2,(DQIB)_67") (pintype "bidirectional"))
    )
    (net (code "43") (name "/IO68") (class "Default")
      (node (ref "P3") (pin "35") (pinfunction "35_35") (pintype "passive"))
      (node (ref "U1") (pin "68") (pinfunction "IO,DIFFIO_B20n,(DQS0B/CQ1B,DPCLK3)_68") (pintype "bidirectional"))
    )
    (net (code "44") (name "/IO69") (class "Default")
      (node (ref "P3") (pin "36") (pinfunction "36_36") (pintype "passive"))
      (node (ref "U1") (pin "69") (pinfunction "IO_69") (pintype "bidirectional"))
    )
    (net (code "45") (name "/IO70") (class "Default")
      (node (ref "P3") (pin "37") (pinfunction "37_37") (pintype "passive"))
      (node (ref "U1") (pin "70") (pinfunction "IO,DIFFIO_B21p_70") (pintype "bidirectional"))
    )
    (net (code "46") (name "/IO71") (class "Default")
      (node (ref "P3") (pin "38") (pinfunction "38_38") (pintype "passive"))
      (node (ref "U1") (pin "71") (pinfunction "IO,DIFFIO_B21n_71") (pintype "bidirectional"))
    )
    (net (code "47") (name "/IO72") (class "Default")
      (node (ref "R10") (pin "2") (pinfunction "2_2") (pintype "passive"))
      (node (ref "U1") (pin "72") (pinfunction "IO,DIFFIO_B22p_72") (pintype "bidirectional"))
    )
    (net (code "48") (name "/IO73") (class "Default")
      (node (ref "R11") (pin "2") (pinfunction "2_2") (pintype "passive"))
      (node (ref "U1") (pin "73") (pinfunction "IO_73") (pintype "bidirectional"))
    )
    (net (code "49") (name "/IO74") (class "Default")
      (node (ref "P4") (pin "4") (pinfunction "4_4") (pintype "passive"))
      (node (ref "U1") (pin "74") (pinfunction "IO_74") (pintype "bidirectional"))
    )
    (net (code "50") (name "/IO75") (class "Default")
      (node (ref "P4") (pin "3") (pinfunction "3_3") (pintype "passive"))
      (node (ref "U1") (pin "75") (pinfunction "IO_75") (pintype "bidirectional"))
    )
    (net (code "51") (name "/IO76") (class "Default")
      (node (ref "P4") (pin "6") (pinfunction "6_6") (pintype "passive"))
      (node (ref "U1") (pin "76") (pinfunction "IO,RUP3_76") (pintype "bidirectional"))
    )
    (net (code "52") (name "/IO77") (class "Default")
      (node (ref "P4") (pin "5") (pinfunction "5_5") (pintype "passive"))
      (node (ref "U1") (pin "77") (pinfunction "IO,RDN3_77") (pintype "bidirectional"))
    )
    (net (code "53") (name "/IO80") (class "Default")
      (node (ref "P4") (pin "8") (pinfunction "8_8") (pintype "passive"))
      (node (ref "U1") (pin "80") (pinfunction "IO,VREFB5N0_80") (pintype "bidirectional"))
    )
    (net (code "54") (name "/IO83") (class "Default")
      (node (ref "P4") (pin "7") (pinfunction "7_7") (pintype "passive"))
      (node (ref "U1") (pin "83") (pinfunction "IO_83") (pintype "bidirectional"))
    )
    (net (code "55") (name "/IO84") (class "Default")
      (node (ref "P4") (pin "10") (pinfunction "10_10") (pintype "passive"))
      (node (ref "U1") (pin "84") (pinfunction "IO,DIFFIO_R8n_84") (pintype "bidirectional"))
    )
    (net (code "56") (name "/IO85") (class "Default")
      (node (ref "P4") (pin "9") (pinfunction "9_9") (pintype "passive"))
      (node (ref "U1") (pin "85") (pinfunction "IO,DIFFIO_R8p,(DQS1R/CQ1R#,DPCLK4)_85") (pintype "bidirectional"))
    )
    (net (code "57") (name "/IO86") (class "Default")
      (node (ref "P4") (pin "12") (pinfunction "12_12") (pintype "passive"))
      (node (ref "U1") (pin "86") (pinfunction "IO,DIFFIO_R7n(DEV_OE)_86") (pintype "bidirectional"))
    )
    (net (code "58") (name "/IO87") (class "Default")
      (node (ref "P4") (pin "11") (pinfunction "11_11") (pintype "passive"))
      (node (ref "U1") (pin "87") (pinfunction "IO,DIFFIO_R7p,(DEV_CLRn)_87") (pintype "bidirectional"))
    )
    (net (code "59") (name "/IO98") (class "Default")
      (node (ref "P4") (pin "16") (pinfunction "16_16") (pintype "passive"))
      (node (ref "U1") (pin "98") (pinfunction "IO,DIFFIO_R4n,(INIT_DONE)_98") (pintype "bidirectional"))
    )
    (net (code "60") (name "/IO99") (class "Default")
      (node (ref "P4") (pin "15") (pinfunction "15_15") (pintype "passive"))
      (node (ref "U1") (pin "99") (pinfunction "IO,DIFFIO_R4p,(CRC_ERROR)_99") (pintype "bidirectional"))
    )
    (net (code "61") (name "/IO100") (class "Default")
      (node (ref "D2") (pin "2") (pinfunction "K_2") (pintype "passive"))
      (node (ref "U1") (pin "100") (pinfunction "IO_100") (pintype "bidirectional"))
      (node (ref "U6") (pin "6") (pinfunction "TXD_6") (pintype "passive"))
    )
    (net (code "62") (name "/IO101") (class "Default")
      (node (ref "D1") (pin "2") (pinfunction "K_2") (pintype "passive"))
      (node (ref "U1") (pin "101") (pinfunction "IO,DIFFIO_R3n,(nCEO)_101") (pintype "bidirectional"))
      (node (ref "U6") (pin "7") (pinfunction "RXD_7") (pintype "passive"))
    )
    (net (code "63") (name "/IO103") (class "Default")
      (node (ref "P4") (pin "18") (pinfunction "18_18") (pintype "passive"))
      (node (ref "U1") (pin "103") (pinfunction "IO,DIFFIO_R3p,(CLKUSR)_103") (pintype "bidirectional"))
    )
    (net (code "64") (name "/IO104") (class "Default")
      (node (ref "P4") (pin "17") (pinfunction "17_17") (pintype "passive"))
      (node (ref "U1") (pin "104") (pinfunction "IO,(DQS0R/CQ1R,DPCLK5)_104") (pintype "bidirectional"))
    )
    (net (code "65") (name "/IO105") (class "Default")
      (node (ref "U1") (pin "105") (pinfunction "IO,VREFB6N0_105") (pintype "bidirectional"))
      (node (ref "U7") (pin "6") (pinfunction "DC_6") (pintype "input"))
    )
    (net (code "66") (name "/IO106") (class "Default")
      (node (ref "P4") (pin "20") (pinfunction "20_20") (pintype "passive"))
      (node (ref "U1") (pin "106") (pinfunction "IO,DIFFIO_R1n_106") (pintype "bidirectional"))
    )
    (net (code "67") (name "/IO110") (class "Default")
      (node (ref "U1") (pin "110") (pinfunction "IO,DIFFIO_T20p,(DQS0T/CQ1T,DPCLK6)_110") (pintype "bidirectional"))
      (node (ref "U7") (pin "5") (pinfunction "RES_5") (pintype "input"))
    )
    (net (code "68") (name "/IO111") (class "Default")
      (node (ref "P4") (pin "19") (pinfunction "19_19") (pintype "passive"))
      (node (ref "U1") (pin "111") (pinfunction "IO,DIFFIO_T19p_111") (pintype "bidirectional"))
    )
    (net (code "69") (name "/IO112") (class "Default")
      (node (ref "U1") (pin "112") (pinfunction "IO,PLL2_CLKOUTn_112") (pintype "bidirectional"))
      (node (ref "U7") (pin "4") (pinfunction "MOSI_4") (pintype "input"))
    )
    (net (code "70") (name "/IO113") (class "Default")
      (node (ref "P4") (pin "21") (pinfunction "21_21") (pintype "passive"))
      (node (ref "U1") (pin "113") (pinfunction "IO,PLL2CLKOUTp_113") (pintype "bidirectional"))
    )
    (net (code "71") (name "/IO114") (class "Default")
      (node (ref "P4") (pin "22") (pinfunction "22_22") (pintype "passive"))
      (node (ref "U1") (pin "114") (pinfunction "IO,RUP4,(DQ1T)_114") (pintype "bidirectional"))
    )
    (net (code "72") (name "/IO115") (class "Default")
      (node (ref "U1") (pin "115") (pinfunction "IO,RUN4,(DQ1T)_115") (pintype "bidirectional"))
      (node (ref "U7") (pin "3") (pinfunction "CLK_3") (pintype "input"))
    )
    (net (code "73") (name "/IO119") (class "Default")
      (node (ref "P4") (pin "23") (pinfunction "23_23") (pintype "passive"))
      (node (ref "U1") (pin "119") (pinfunction "IO,VREFB7N0_119") (pintype "bidirectional"))
    )
    (net (code "74") (name "/IO120") (class "Default")
      (node (ref "P4") (pin "24") (pinfunction "24_24") (pintype "passive"))
      (node (ref "U1") (pin "120") (pinfunction "IO,DIFFIO_T16n,(DQ1T)_120") (pintype "bidirectional"))
    )
    (net (code "75") (name "/IO121") (class "Default")
      (node (ref "P4") (pin "25") (pinfunction "25_25") (pintype "passive"))
      (node (ref "U1") (pin "121") (pinfunction "IO,DIFFIO_T16p_121") (pintype "bidirectional"))
    )
    (net (code "76") (name "/IO124") (class "Default")
      (node (ref "P4") (pin "26") (pinfunction "26_26") (pintype "passive"))
      (node (ref "U1") (pin "124") (pinfunction "IO,DIFFIO_T13p_124") (pintype "bidirectional"))
    )
    (net (code "77") (name "/IO125") (class "Default")
      (node (ref "P4") (pin "27") (pinfunction "27_27") (pintype "passive"))
      (node (ref "U1") (pin "125") (pinfunction "IO_125") (pintype "bidirectional"))
    )
    (net (code "78") (name "/IO126") (class "Default")
      (node (ref "P4") (pin "28") (pinfunction "28_28") (pintype "passive"))
      (node (ref "U1") (pin "126") (pinfunction "IO,DIFFIO_T12n_126") (pintype "bidirectional"))
    )
    (net (code "79") (name "/IO127") (class "Default")
      (node (ref "P4") (pin "29") (pinfunction "29_29") (pintype "passive"))
      (node (ref "U1") (pin "127") (pinfunction "IO,DIFFIO_T12p_127") (pintype "bidirectional"))
    )
    (net (code "80") (name "/IO128") (class "Default")
      (node (ref "P4") (pin "30") (pinfunction "30_30") (pintype "passive"))
      (node (ref "U1") (pin "128") (pinfunction "IO,DIFFIO_T11n_128") (pintype "bidirectional"))
    )
    (net (code "81") (name "/IO129") (class "Default")
      (node (ref "P4") (pin "31") (pinfunction "31_31") (pintype "passive"))
      (node (ref "U1") (pin "129") (pinfunction "IO,DIFFIO_T11p_129") (pintype "bidirectional"))
    )
    (net (code "82") (name "/IO132") (class "Default")
      (node (ref "P4") (pin "32") (pinfunction "32_32") (pintype "passive"))
      (node (ref "U1") (pin "132") (pinfunction "IO,DIFFIO_T10n,(DATA2),(DQ1T)_132") (pintype "bidirectional"))
    )
    (net (code "83") (name "/IO133") (class "Default")
      (node (ref "P4") (pin "34") (pinfunction "34_34") (pintype "passive"))
      (node (ref "U1") (pin "133") (pinfunction "IO,DIFFIO_T10p,(DATA3),(DQ1T)_133") (pintype "bidirectional"))
    )
    (net (code "84") (name "/IO135") (class "Default")
      (node (ref "P4") (pin "33") (pinfunction "33_33") (pintype "passive"))
      (node (ref "U1") (pin "135") (pinfunction "IO,DIFFIO_T8n,(DQ1T)_135") (pintype "bidirectional"))
    )
    (net (code "85") (name "/IO136") (class "Default")
      (node (ref "P4") (pin "36") (pinfunction "36_36") (pintype "passive"))
      (node (ref "U1") (pin "136") (pinfunction "IO,VREFB8N0_136") (pintype "bidirectional"))
    )
    (net (code "86") (name "/IO137") (class "Default")
      (node (ref "P4") (pin "35") (pinfunction "35_35") (pintype "passive"))
      (node (ref "U1") (pin "137") (pinfunction "IO,(DATA5),(DQ1T)_137") (pintype "bidirectional"))
    )
    (net (code "87") (name "/IO138") (class "Default")
      (node (ref "P4") (pin "38") (pinfunction "38_38") (pintype "passive"))
      (node (ref "U1") (pin "138") (pinfunction "IO,(DATA6)_138") (pintype "bidirectional"))
    )
    (net (code "88") (name "/IO139") (class "Default")
      (node (ref "P4") (pin "37") (pinfunction "37_37") (pintype "passive"))
      (node (ref "U1") (pin "141") (pinfunction "IO,DIFFIO_T5p_141") (pintype "bidirectional"))
    )
    (net (code "89") (name "/KEY0") (class "Default")
      (node (ref "R12") (pin "2") (pinfunction "2_2") (pintype "passive"))
      (node (ref "S0") (pin "1") (pinfunction "1_1") (pintype "passive"))
      (node (ref "U1") (pin "89") (pinfunction "CLK6,DIFFCLK_3p_89") (pintype "input"))
    )
    (net (code "90") (name "/KEY1") (class "Default")
      (node (ref "R17") (pin "2") (pinfunction "2_2") (pintype "passive"))
      (node (ref "S1") (pin "1") (pinfunction "1_1") (pintype "passive"))
      (node (ref "U1") (pin "88") (pinfunction "CLK7,DIFFCLK_3n_88") (pintype "input"))
    )
    (net (code "91") (name "/RESET") (class "Default")
      (node (ref "R16") (pin "2") (pinfunction "2_2") (pintype "passive"))
      (node (ref "S2") (pin "1") (pinfunction "1_1") (pintype "passive"))
      (node (ref "U1") (pin "25") (pinfunction "CLK3,DIFFCLK_1n_25") (pintype "input"))
    )
    (net (code "92") (name "/TCK") (class "Default")
      (node (ref "P5") (pin "1") (pinfunction "1_1") (pintype "passive"))
      (node (ref "R9") (pin "2") (pinfunction "2_2") (pintype "passive"))
      (node (ref "U1") (pin "16") (pinfunction "TCK_16") (pintype "input"))
    )
    (net (code "93") (name "/TDI") (class "Default")
      (node (ref "P5") (pin "9") (pinfunction "9_9") (pintype "passive"))
      (node (ref "R13") (pin "2") (pinfunction "2_2") (pintype "passive"))
      (node (ref "U1") (pin "15") (pinfunction "TDI_15") (pintype "input"))
    )
    (net (code "94") (name "/TDO") (class "Default")
      (node (ref "P5") (pin "3") (pinfunction "3_3") (pintype "passive"))
      (node (ref "R15") (pin "2") (pinfunction "2_2") (pintype "passive"))
      (node (ref "U1") (pin "20") (pinfunction "TDO_20") (pintype "output"))
    )
    (net (code "95") (name "/TMS") (class "Default")
      (node (ref "P5") (pin "5") (pinfunction "5_5") (pintype "passive"))
      (node (ref "R14") (pin "2") (pinfunction "2_2") (pintype "passive"))
      (node (ref "U1") (pin "18") (pinfunction "TMS_18") (pintype "input"))
    )
    (net (code "96") (name "/USB D+") (class "Default")
      (node (ref "U6") (pin "1") (pinfunction "UD+_1") (pintype "passive"))
      (node (ref "USB") (pin "3") (pinfunction "D+_3") (pintype "passive"))
    )
    (net (code "97") (name "/USB D-") (class "Default")
      (node (ref "U6") (pin "2") (pinfunction "UD-_2") (pintype "passive"))
      (node (ref "USB") (pin "2") (pinfunction "D-_2") (pintype "passive"))
    )
    (net (code "98") (name "/nCEO") (class "Default")
      (node (ref "U1") (pin "8") (pinfunction "IO,DIFFIO_L2P,(FLASH_NCE,NCEO)_8") (pintype "bidirectional"))
      (node (ref "U5") (pin "1") (pinfunction "nCS_1") (pintype "input"))
    )
    (net (code "99") (name "GND") (class "Default")
      (node (ref "C1") (pin "1") (pinfunction "1_1") (pintype "passive"))
      (node (ref "C10") (pin "1") (pinfunction "1_1") (pintype "passive"))
      (node (ref "C11") (pin "1") (pinfunction "1_1") (pintype "passive"))
      (node (ref "C12") (pin "1") (pinfunction "1_1") (pintype "passive"))
      (node (ref "C13") (pin "1") (pinfunction "1_1") (pintype "passive"))
      (node (ref "C14") (pin "1") (pinfunction "1_1") (pintype "passive"))
      (node (ref "C15") (pin "1") (pinfunction "1_1") (pintype "passive"))
      (node (ref "C16") (pin "1") (pinfunction "1_1") (pintype "passive"))
      (node (ref "C17") (pin "1") (pinfunction "1_1") (pintype "passive"))
      (node (ref "C18") (pin "1") (pinfunction "1_1") (pintype "passive"))
      (node (ref "C19") (pin "1") (pinfunction "1_1") (pintype "passive"))
      (node (ref "C2") (pin "1") (pinfunction "1_1") (pintype "passive"))
      (node (ref "C20") (pin "1") (pinfunction "1_1") (pintype "passive"))
      (node (ref "C21") (pin "1") (pinfunction "1_1") (pintype "passive"))
      (node (ref "C22") (pin "1") (pinfunction "1_1") (pintype "passive"))
      (node (ref "C23") (pin "1") (pinfunction "1_1") (pintype "passive"))
      (node (ref "C24") (pin "1") (pinfunction "1_1") (pintype "passive"))
      (node (ref "C25") (pin "1") (pinfunction "1_1") (pintype "passive"))
      (node (ref "C26") (pin "1") (pinfunction "1_1") (pintype "passive"))
      (node (ref "C27") (pin "1") (pinfunction "1_1") (pintype "passive"))
      (node (ref "C28") (pin "1") (pinfunction "1_1") (pintype "passive"))
      (node (ref "C3") (pin "1") (pinfunction "1_1") (pintype "passive"))
      (node (ref "C4") (pin "1") (pinfunction "1_1") (pintype "passive"))
      (node (ref "C5") (pin "1") (pinfunction "1_1") (pintype "passive"))
      (node (ref "C6") (pin "1") (pinfunction "1_1") (pintype "passive"))
      (node (ref "C7") (pin "1") (pinfunction "1_1") (pintype "passive"))
      (node (ref "C8") (pin "1") (pinfunction "1_1") (pintype "passive"))
      (node (ref "C9") (pin "1") (pinfunction "1_1") (pintype "passive"))
      (node (ref "D3") (pin "2") (pinfunction "K_2") (pintype "passive"))
      (node (ref "D4") (pin "2") (pinfunction "K_2") (pintype "passive"))
      (node (ref "D5") (pin "2") (pinfunction "K_2") (pintype "passive"))
      (node (ref "P3") (pin "2") (pinfunction "2_2") (pintype "passive"))
      (node (ref "P3") (pin "40") (pinfunction "40_40") (pintype "passive"))
      (node (ref "P4") (pin "2") (pinfunction "2_2") (pintype "passive"))
      (node (ref "P4") (pin "40") (pinfunction "40_40") (pintype "passive"))
      (node (ref "P5") (pin "10") (pinfunction "10_10") (pintype "passive"))
      (node (ref "P5") (pin "2") (pinfunction "2_2") (pintype "passive"))
      (node (ref "R5") (pin "1") (pinfunction "1_1") (pintype "passive"))
      (node (ref "R9") (pin "1") (pinfunction "1_1") (pintype "passive"))
      (node (ref "S0") (pin "2") (pinfunction "2_2") (pintype "passive"))
      (node (ref "S1") (pin "2") (pinfunction "2_2") (pintype "passive"))
      (node (ref "S2") (pin "2") (pinfunction "2_2") (pintype "passive"))
      (node (ref "U1") (pin "108") (pinfunction "GNDA2_108") (pintype "power_in"))
      (node (ref "U1") (pin "118") (pinfunction "GND_118") (pintype "power_in"))
      (node (ref "U1") (pin "123") (pinfunction "GND_123") (pintype "power_in"))
      (node (ref "U1") (pin "131") (pinfunction "GND_131") (pintype "power_in"))
      (node (ref "U1") (pin "140") (pinfunction "GND_140") (pintype "power_in"))
      (node (ref "U1") (pin "145") (pinfunction "TH_PAD_145") (pintype "passive"))
      (node (ref "U1") (pin "19") (pinfunction "GND_19") (pintype "power_in"))
      (node (ref "U1") (pin "22") (pinfunction "GND_22") (pintype "power_in"))
      (node (ref "U1") (pin "27") (pinfunction "GND_27") (pintype "power_in"))
      (node (ref "U1") (pin "36") (pinfunction "GNDA1_36") (pintype "power_in"))
      (node (ref "U1") (pin "4") (pinfunction "GND_4") (pintype "power_in"))
      (node (ref "U1") (pin "41") (pinfunction "GND_41") (pintype "power_in"))
      (node (ref "U1") (pin "48") (pinfunction "GND_48") (pintype "power_in"))
      (node (ref "U1") (pin "57") (pinfunction "GND_57") (pintype "power_in"))
      (node (ref "U1") (pin "63") (pinfunction "GND_63") (pintype "power_in"))
      (node (ref "U1") (pin "79") (pinfunction "GND_79") (pintype "power_in"))
      (node (ref "U1") (pin "82") (pinfunction "GND_82") (pintype "power_in"))
      (node (ref "U1") (pin "94") (pinfunction "MSEL0_94") (pintype "input"))
      (node (ref "U1") (pin "95") (pinfunction "GND_95") (pintype "power_in"))
      (node (ref "U1") (pin "97") (pinfunction "MSEL2_97") (pintype "input"))
      (node (ref "U2") (pin "1") (pinfunction "GND_1") (pintype "passive"))
      (node (ref "U3") (pin "1") (pinfunction "GND_1") (pintype "passive"))
      (node (ref "U4") (pin "1") (pinfunction "GND_1") (pintype "passive"))
      (node (ref "U5") (pin "4") (pinfunction "GND_4") (pintype "power_in"))
      (node (ref "U6") (pin "3") (pinfunction "GND_3") (pintype "passive"))
      (node (ref "U7") (pin "1") (pinfunction "GND_1") (pintype "power_in"))
      (node (ref "U7") (pin "7") (pinfunction "CS_7") (pintype "input"))
      (node (ref "USB") (pin "5") (pinfunction "GND_5") (pintype "passive"))
      (node (ref "Y2") (pin "2") (pinfunction "GND_2") (pintype "power_in"))
    )
    (net (code "100") (name "Net-(D1-A)") (class "Default")
      (node (ref "D1") (pin "1") (pinfunction "A_1") (pintype "passive"))
      (node (ref "R6") (pin "1") (pinfunction "1_1") (pintype "passive"))
    )
    (net (code "101") (name "Net-(D2-A)") (class "Default")
      (node (ref "D2") (pin "1") (pinfunction "A_1") (pintype "passive"))
      (node (ref "R7") (pin "1") (pinfunction "1_1") (pintype "passive"))
    )
    (net (code "102") (name "Net-(D3-A)") (class "Default")
      (node (ref "D3") (pin "1") (pinfunction "A_1") (pintype "passive"))
      (node (ref "R8") (pin "1") (pinfunction "1_1") (pintype "passive"))
    )
    (net (code "103") (name "Net-(D4-A)") (class "Default")
      (node (ref "D4") (pin "1") (pinfunction "A_1") (pintype "passive"))
      (node (ref "R10") (pin "1") (pinfunction "1_1") (pintype "passive"))
    )
    (net (code "104") (name "Net-(D5-A)") (class "Default")
      (node (ref "D5") (pin "1") (pinfunction "A_1") (pintype "passive"))
      (node (ref "R11") (pin "1") (pinfunction "1_1") (pintype "passive"))
    )
    (net (code "105") (name "Net-(U1J-CONF_DONE)") (class "Default")
      (node (ref "R4") (pin "2") (pinfunction "2_2") (pintype "passive"))
      (node (ref "U1") (pin "92") (pinfunction "CONF_DONE_92") (pintype "bidirectional"))
    )
    (net (code "106") (name "Net-(U1J-nCE)") (class "Default")
      (node (ref "R5") (pin "2") (pinfunction "2_2") (pintype "passive"))
      (node (ref "U1") (pin "21") (pinfunction "nCE_21") (pintype "input"))
    )
    (net (code "107") (name "Net-(U1J-nCONFIG)") (class "Default")
      (node (ref "R3") (pin "2") (pinfunction "2_2") (pintype "passive"))
      (node (ref "U1") (pin "14") (pinfunction "nCONFIG_14") (pintype "input"))
    )
    (net (code "108") (name "Net-(U1J-nSTATUS)") (class "Default")
      (node (ref "R2") (pin "2") (pinfunction "2_2") (pintype "passive"))
      (node (ref "U1") (pin "9") (pinfunction "nSTATUS_9") (pintype "bidirectional"))
    )
    (net (code "109") (name "Net-(U5-CLK)") (class "Default")
      (node (ref "R19") (pin "2") (pinfunction "2_2") (pintype "passive"))
      (node (ref "U5") (pin "6") (pinfunction "CLK_6") (pintype "input"))
    )
    (net (code "110") (name "Net-(U5-DQ1)") (class "Default")
      (node (ref "R18") (pin "1") (pinfunction "1_1") (pintype "passive"))
      (node (ref "U5") (pin "2") (pinfunction "DQ1_2") (pintype "bidirectional"))
    )
    (net (code "111") (name "Net-(U6-V3)") (class "Default")
      (node (ref "C28") (pin "2") (pinfunction "2_2") (pintype "passive"))
      (node (ref "U6") (pin "8") (pinfunction "V3_8") (pintype "passive"))
    )
    (net (code "112") (name "Net-(USB-+5V)") (class "Default")
      (node (ref "R1") (pin "1") (pinfunction "1_1") (pintype "passive"))
      (node (ref "USB") (pin "1") (pinfunction "+5V_1") (pintype "passive"))
    )
    (net (code "113") (name "unconnected-(P5-Pad7)") (class "Default")
      (node (ref "P5") (pin "7") (pinfunction "7_7") (pintype "passive+no_connect"))
    )
    (net (code "114") (name "unconnected-(P5-Pad8)") (class "Default")
      (node (ref "P5") (pin "8") (pinfunction "8_8") (pintype "passive+no_connect"))
    )
    (net (code "115") (name "unconnected-(U1H-IO,DIFFIO_T1n,(DQ1T)-Pad143)") (class "Default")
      (node (ref "U1") (pin "143") (pinfunction "IO,DIFFIO_T1n,(DQ1T)_143") (pintype "bidirectional+no_connect"))
    )
    (net (code "116") (name "unconnected-(U1H-IO,DIFFIO_T1p,(DM1T)-Pad144)") (class "Default")
      (node (ref "U1") (pin "144") (pinfunction "IO,DIFFIO_T1p,(DM1T)_144") (pintype "bidirectional+no_connect"))
    )
    (net (code "117") (name "unconnected-(U1H-IO,DIFFIO_T2p,(DQS1T{slash}CQ1T#,DPCLK7)-Pad142)") (class "Default")
      (node (ref "U1") (pin "142") (pinfunction "IO,DIFFIO_T2p,(DQS1T/CQ1T#,DPCLK7)_142") (pintype "bidirectional+no_connect"))
    )
    (net (code "118") (name "unconnected-(U1I-CLK2,DIFFCLK_1p-Pad24)") (class "Default")
      (node (ref "U1") (pin "24") (pinfunction "CLK2,DIFFCLK_1p_24") (pintype "input+no_connect"))
    )
    (net (code "119") (name "unconnected-(U6-RTS-Pad4)") (class "Default")
      (node (ref "U6") (pin "4") (pinfunction "RTS_4") (pintype "passive+no_connect"))
    )
    (net (code "120") (name "unconnected-(USB-ID-Pad4)") (class "Default")
      (node (ref "USB") (pin "4") (pinfunction "ID_4") (pintype "passive+no_connect"))
    )
    (net (code "121") (name "unconnected-(Y2-NC-Pad1)") (class "Default")
      (node (ref "Y2") (pin "1") (pinfunction "NC_1") (pintype "passive+no_connect"))
    )
  )
)
